# Sheet1.net
KiCad netlist of a schematic drawn in Altium Designer
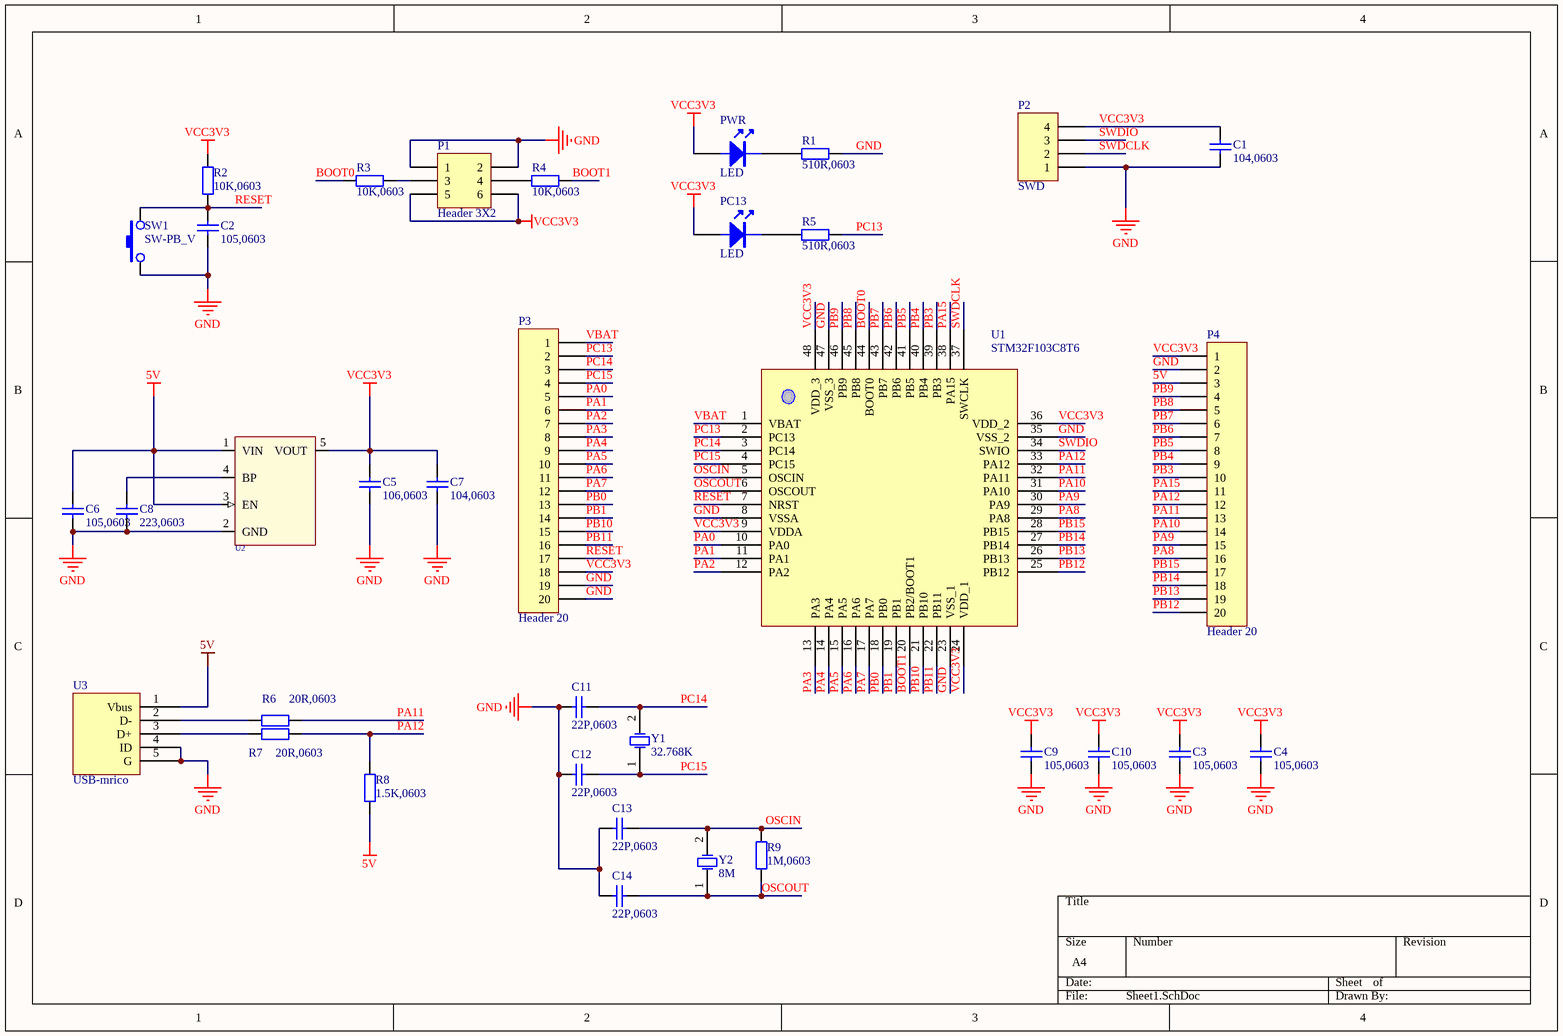
[diagram p0: Sheet1.SchDoc]

(export (version "E")
  (design (tool "Eeschema 10.0.6"))
  (components
    (comp (ref "C1")
      (value "104,0603")
      (footprint "C 0603")
      (description "Capacitor")
      (fields (field (name "PUBLISHER") "Altium Limited"))
      (libsource (lib "STM32F103C8T6") (part "Cap"))
    )
    (comp (ref "C2")
      (value "105,0603")
      (footprint "C 0603")
      (description "Capacitor")
      (fields (field (name "PUBLISHER") "Altium Limited"))
      (libsource (lib "STM32F103C8T6") (part "Cap"))
    )
    (comp (ref "C3")
      (value "105,0603")
      (footprint "C 0603")
      (description "Capacitor")
      (fields (field (name "PUBLISHER") "Altium Limited"))
      (libsource (lib "STM32F103C8T6") (part "Cap"))
    )
    (comp (ref "C4")
      (value "105,0603")
      (footprint "C 0603")
      (description "Capacitor")
      (fields (field (name "PUBLISHER") "Altium Limited"))
      (libsource (lib "STM32F103C8T6") (part "Cap"))
    )
    (comp (ref "C5")
      (value "106,0603")
      (footprint "C 0603")
      (description "Capacitor")
      (fields (field (name "PUBLISHER") "Altium Limited"))
      (libsource (lib "STM32F103C8T6") (part "Cap"))
    )
    (comp (ref "C6")
      (value "105,0603")
      (footprint "C 0603")
      (description "Capacitor")
      (fields (field (name "PUBLISHER") "Altium Limited"))
      (libsource (lib "STM32F103C8T6") (part "Cap"))
    )
    (comp (ref "C7")
      (value "104,0603")
      (footprint "C 0603")
      (description "Capacitor")
      (fields (field (name "PUBLISHER") "Altium Limited"))
      (libsource (lib "STM32F103C8T6") (part "Cap"))
    )
    (comp (ref "C8")
      (value "223,0603")
      (footprint "C 0603")
      (description "Capacitor")
      (fields (field (name "PUBLISHER") "Altium Limited"))
      (libsource (lib "STM32F103C8T6") (part "Cap"))
    )
    (comp (ref "C9")
      (value "105,0603")
      (footprint "C 0603")
      (description "Capacitor")
      (fields (field (name "PUBLISHER") "Altium Limited"))
      (libsource (lib "STM32F103C8T6") (part "Cap"))
    )
    (comp (ref "C10")
      (value "105,0603")
      (footprint "C 0603")
      (description "Capacitor")
      (fields (field (name "PUBLISHER") "Altium Limited"))
      (libsource (lib "STM32F103C8T6") (part "Cap"))
    )
    (comp (ref "C11")
      (value "22P,0603")
      (footprint "C 0603")
      (description "Capacitor")
      (fields (field (name "PUBLISHER") "Altium Limited"))
      (libsource (lib "STM32F103C8T6") (part "Cap"))
    )
    (comp (ref "C12")
      (value "22P,0603")
      (footprint "C 0603")
      (description "Capacitor")
      (fields (field (name "PUBLISHER") "Altium Limited"))
      (libsource (lib "STM32F103C8T6") (part "Cap"))
    )
    (comp (ref "C13")
      (value "22P,0603")
      (footprint "C 0603")
      (description "Capacitor")
      (fields (field (name "PUBLISHER") "Altium Limited"))
      (libsource (lib "STM32F103C8T6") (part "Cap"))
    )
    (comp (ref "C14")
      (value "22P,0603")
      (footprint "C 0603")
      (description "Capacitor")
      (fields (field (name "PUBLISHER") "Altium Limited"))
      (libsource (lib "STM32F103C8T6") (part "Cap"))
    )
    (comp (ref "P1")
      (value "Header 3X2")
      (footprint "HDR-3X2")
      (description "Header, 3-Pin, Dual row")
      (fields (field (name "PUBLISHER") "Altium Limited"))
      (libsource (lib "STM32F103C8T6") (part "Header 3X2"))
    )
    (comp (ref "P2")
      (value "SWD")
      (footprint "HDR-1X4_H")
      (description "Header, 4-Pin")
      (fields (field (name "PUBLISHER") "Altium Limited"))
      (libsource (lib "STM32F103C8T6") (part "Header 4"))
    )
    (comp (ref "P3")
      (value "Header 20")
      (footprint "HDR1X20")
      (description "Header, 20-Pin")
      (fields (field (name "PUBLISHER") "Altium Limited"))
      (libsource (lib "STM32F103C8T6") (part "Header 20"))
    )
    (comp (ref "P4")
      (value "Header 20")
      (footprint "HDR1X20")
      (description "Header, 20-Pin")
      (fields (field (name "PUBLISHER") "Altium Limited"))
      (libsource (lib "") (part "Header 20_1"))
    )
    (comp (ref "PC13") (value "LED") (footprint "LED 0805G") (libsource (lib "STM32F103C8T6") (part "LED")))
    (comp (ref "PWR") (value "LED") (footprint "LED 0805G") (libsource (lib "STM32F103C8T6") (part "LED")))
    (comp (ref "R1")
      (value "510R,0603")
      (footprint "R 0603")
      (description "Resistor")
      (fields (field (name "PUBLISHER") "Altium Limited"))
      (libsource (lib "STM32F103C8T6") (part "Res2"))
    )
    (comp (ref "R2")
      (value "10K,0603")
      (footprint "R 0603")
      (description "Resistor")
      (fields (field (name "PUBLISHER") "Altium Limited"))
      (libsource (lib "") (part "Res2_1"))
    )
    (comp (ref "R3")
      (value "10K,0603")
      (footprint "R 0603")
      (description "Resistor")
      (fields (field (name "PUBLISHER") "Altium Limited"))
      (libsource (lib "STM32F103C8T6") (part "Res2"))
    )
    (comp (ref "R4")
      (value "10K,0603")
      (footprint "R 0603")
      (description "Resistor")
      (fields (field (name "PUBLISHER") "Altium Limited"))
      (libsource (lib "STM32F103C8T6") (part "Res2"))
    )
    (comp (ref "R5")
      (value "510R,0603")
      (footprint "R 0603")
      (description "Resistor")
      (fields (field (name "PUBLISHER") "Altium Limited"))
      (libsource (lib "STM32F103C8T6") (part "Res2"))
    )
    (comp (ref "R6")
      (value "20R,0603")
      (footprint "R 0603")
      (description "Resistor")
      (fields (field (name "PUBLISHER") "Altium Limited"))
      (libsource (lib "STM32F103C8T6") (part "Res2"))
    )
    (comp (ref "R7")
      (value "20R,0603")
      (footprint "R 0603")
      (description "Resistor")
      (fields (field (name "PUBLISHER") "Altium Limited"))
      (libsource (lib "STM32F103C8T6") (part "Res2"))
    )
    (comp (ref "R8")
      (value "1.5K,0603")
      (footprint "R 0603")
      (description "Resistor")
      (fields (field (name "PUBLISHER") "Altium Limited"))
      (libsource (lib "") (part "Res2_1"))
    )
    (comp (ref "R9")
      (value "1M,0603")
      (footprint "R 0603")
      (description "Resistor")
      (fields (field (name "PUBLISHER") "Altium Limited"))
      (libsource (lib "") (part "Res2_1"))
    )
    (comp (ref "SW1")
      (value "SW-PB_V")
      (footprint "TSW SMD-3*6*2.5")
      (description "SWITCH")
      (libsource (lib "STM32F103C8T6") (part "SW-PB_V"))
    )
    (comp (ref "U1")
      (value "STM32F103C8T6")
      (footprint "TQFP48 7x7_L")
      (libsource (lib "STM32F103C8T6") (part "STM32F103C8T6"))
    )
    (comp (ref "U2")
      (value "RT9193")
      (footprint "SOT23-5L")
      (fields (field (name "ICA_PARTNUM") "$$2191094$$RT9193-15CU5") (field (name "PART NUMBER") "TMP-13"))
      (libsource (lib "STM32F103C8T6") (part "RT9193X_5P"))
    )
    (comp (ref "U3")
      (value "USB-mrico")
      (footprint "USB-micro_B")
      (libsource (lib "PCB_Project_4") (part "usb-STM"))
    )
    (comp (ref "Y1")
      (value "32.768K")
      (footprint "XTAL-3215")
      (description "Crystal Oscillator")
      (fields (field (name "PUBLISHER") "Altium Limited"))
      (libsource (lib "PCB_Project_4") (part "XTAL"))
    )
    (comp (ref "Y2")
      (value "8M")
      (footprint "STM32F103C8T6核心板:XTAL-5032")
      (description "Crystal Oscillator")
      (fields (field (name "PUBLISHER") "Altium Limited"))
      (libsource (lib "PCB_Project_4") (part "XTAL"))
    )
  )
  (nets
    (net (code "1") (name "/BOOT0") (class "Default")
      (node (ref "R3") (pin "1") (pinfunction "1_1") (pintype "passive"))
      (node (ref "U1") (pin "44") (pinfunction "BOOT0_44") (pintype "passive"))
    )
    (net (code "2") (name "/BOOT1") (class "Default")
      (node (ref "R4") (pin "2") (pinfunction "2_2") (pintype "passive"))
      (node (ref "U1") (pin "20") (pinfunction "PB2/BOOT1_20") (pintype "passive"))
    )
    (net (code "3") (name "/OSCIN") (class "Default")
      (node (ref "C13") (pin "1") (pinfunction "1_1") (pintype "passive"))
      (node (ref "R9") (pin "2") (pinfunction "2_2") (pintype "passive"))
      (node (ref "U1") (pin "5") (pinfunction "OSCIN_5") (pintype "passive"))
      (node (ref "Y2") (pin "2") (pinfunction "OSC2_2") (pintype "passive"))
    )
    (net (code "4") (name "/OSCOUT") (class "Default")
      (node (ref "C14") (pin "1") (pinfunction "1_1") (pintype "passive"))
      (node (ref "R9") (pin "1") (pinfunction "1_1") (pintype "passive"))
      (node (ref "U1") (pin "6") (pinfunction "OSCOUT_6") (pintype "passive"))
      (node (ref "Y2") (pin "1") (pinfunction "OSC1_1") (pintype "passive"))
    )
    (net (code "5") (name "/PA0") (class "Default")
      (node (ref "P3") (pin "5") (pinfunction "5_5") (pintype "passive"))
      (node (ref "U1") (pin "10") (pinfunction "PA0_10") (pintype "passive"))
    )
    (net (code "6") (name "/PA1") (class "Default")
      (node (ref "P3") (pin "6") (pinfunction "6_6") (pintype "passive"))
      (node (ref "U1") (pin "11") (pinfunction "PA1_11") (pintype "passive"))
    )
    (net (code "7") (name "/PA2") (class "Default")
      (node (ref "P3") (pin "7") (pinfunction "7_7") (pintype "passive"))
      (node (ref "U1") (pin "12") (pinfunction "PA2_12") (pintype "passive"))
    )
    (net (code "8") (name "/PA3") (class "Default")
      (node (ref "P3") (pin "8") (pinfunction "8_8") (pintype "passive"))
      (node (ref "U1") (pin "13") (pinfunction "PA3_13") (pintype "passive"))
    )
    (net (code "9") (name "/PA4") (class "Default")
      (node (ref "P3") (pin "9") (pinfunction "9_9") (pintype "passive"))
      (node (ref "U1") (pin "14") (pinfunction "PA4_14") (pintype "passive"))
    )
    (net (code "10") (name "/PA5") (class "Default")
      (node (ref "P3") (pin "10") (pinfunction "10_10") (pintype "passive"))
      (node (ref "U1") (pin "15") (pinfunction "PA5_15") (pintype "passive"))
    )
    (net (code "11") (name "/PA6") (class "Default")
      (node (ref "P3") (pin "11") (pinfunction "11_11") (pintype "passive"))
      (node (ref "U1") (pin "16") (pinfunction "PA6_16") (pintype "passive"))
    )
    (net (code "12") (name "/PA7") (class "Default")
      (node (ref "P3") (pin "12") (pinfunction "12_12") (pintype "passive"))
      (node (ref "U1") (pin "17") (pinfunction "PA7_17") (pintype "passive"))
    )
    (net (code "13") (name "/PA8") (class "Default")
      (node (ref "P4") (pin "16") (pinfunction "16_16") (pintype "passive"))
      (node (ref "U1") (pin "29") (pinfunction "PA8_29") (pintype "passive"))
    )
    (net (code "14") (name "/PA9") (class "Default")
      (node (ref "P4") (pin "15") (pinfunction "15_15") (pintype "passive"))
      (node (ref "U1") (pin "30") (pinfunction "PA9_30") (pintype "passive"))
    )
    (net (code "15") (name "/PA10") (class "Default")
      (node (ref "P4") (pin "14") (pinfunction "14_14") (pintype "passive"))
      (node (ref "U1") (pin "31") (pinfunction "PA10_31") (pintype "passive"))
    )
    (net (code "16") (name "/PA11") (class "Default")
      (node (ref "P4") (pin "13") (pinfunction "13_13") (pintype "passive"))
      (node (ref "R6") (pin "2") (pinfunction "2_2") (pintype "passive"))
      (node (ref "U1") (pin "32") (pinfunction "PA11_32") (pintype "passive"))
    )
    (net (code "17") (name "/PA12") (class "Default")
      (node (ref "P4") (pin "12") (pinfunction "12_12") (pintype "passive"))
      (node (ref "R7") (pin "2") (pinfunction "2_2") (pintype "passive"))
      (node (ref "R8") (pin "2") (pinfunction "2_2") (pintype "passive"))
      (node (ref "U1") (pin "33") (pinfunction "PA12_33") (pintype "passive"))
    )
    (net (code "18") (name "/PA15") (class "Default")
      (node (ref "P4") (pin "11") (pinfunction "11_11") (pintype "passive"))
      (node (ref "U1") (pin "38") (pinfunction "PA15_38") (pintype "passive"))
    )
    (net (code "19") (name "/PB0") (class "Default")
      (node (ref "P3") (pin "13") (pinfunction "13_13") (pintype "passive"))
      (node (ref "U1") (pin "18") (pinfunction "PB0_18") (pintype "passive"))
    )
    (net (code "20") (name "/PB1") (class "Default")
      (node (ref "P3") (pin "14") (pinfunction "14_14") (pintype "passive"))
      (node (ref "U1") (pin "19") (pinfunction "PB1_19") (pintype "passive"))
    )
    (net (code "21") (name "/PB3") (class "Default")
      (node (ref "P4") (pin "10") (pinfunction "10_10") (pintype "passive"))
      (node (ref "U1") (pin "39") (pinfunction "PB3_39") (pintype "passive"))
    )
    (net (code "22") (name "/PB4") (class "Default")
      (node (ref "P4") (pin "9") (pinfunction "9_9") (pintype "passive"))
      (node (ref "U1") (pin "40") (pinfunction "PB4_40") (pintype "passive"))
    )
    (net (code "23") (name "/PB5") (class "Default")
      (node (ref "P4") (pin "8") (pinfunction "8_8") (pintype "passive"))
      (node (ref "U1") (pin "41") (pinfunction "PB5_41") (pintype "passive"))
    )
    (net (code "24") (name "/PB6") (class "Default")
      (node (ref "P4") (pin "7") (pinfunction "7_7") (pintype "passive"))
      (node (ref "U1") (pin "42") (pinfunction "PB6_42") (pintype "passive"))
    )
    (net (code "25") (name "/PB7") (class "Default")
      (node (ref "P4") (pin "6") (pinfunction "6_6") (pintype "passive"))
      (node (ref "U1") (pin "43") (pinfunction "PB7_43") (pintype "passive"))
    )
    (net (code "26") (name "/PB8") (class "Default")
      (node (ref "P4") (pin "5") (pinfunction "5_5") (pintype "passive"))
      (node (ref "U1") (pin "45") (pinfunction "PB8_45") (pintype "passive"))
    )
    (net (code "27") (name "/PB9") (class "Default")
      (node (ref "P4") (pin "4") (pinfunction "4_4") (pintype "passive"))
      (node (ref "U1") (pin "46") (pinfunction "PB9_46") (pintype "passive"))
    )
    (net (code "28") (name "/PB10") (class "Default")
      (node (ref "P3") (pin "15") (pinfunction "15_15") (pintype "passive"))
      (node (ref "U1") (pin "21") (pinfunction "PB10_21") (pintype "passive"))
    )
    (net (code "29") (name "/PB11") (class "Default")
      (node (ref "P3") (pin "16") (pinfunction "16_16") (pintype "passive"))
      (node (ref "U1") (pin "22") (pinfunction "PB11_22") (pintype "passive"))
    )
    (net (code "30") (name "/PB12") (class "Default")
      (node (ref "P4") (pin "20") (pinfunction "20_20") (pintype "passive"))
      (node (ref "U1") (pin "25") (pinfunction "PB12_25") (pintype "passive"))
    )
    (net (code "31") (name "/PB13") (class "Default")
      (node (ref "P4") (pin "19") (pinfunction "19_19") (pintype "passive"))
      (node (ref "U1") (pin "26") (pinfunction "PB13_26") (pintype "passive"))
    )
    (net (code "32") (name "/PB14") (class "Default")
      (node (ref "P4") (pin "18") (pinfunction "18_18") (pintype "passive"))
      (node (ref "U1") (pin "27") (pinfunction "PB14_27") (pintype "passive"))
    )
    (net (code "33") (name "/PB15") (class "Default")
      (node (ref "P4") (pin "17") (pinfunction "17_17") (pintype "passive"))
      (node (ref "U1") (pin "28") (pinfunction "PB15_28") (pintype "passive"))
    )
    (net (code "34") (name "/PC13") (class "Default")
      (node (ref "P3") (pin "2") (pinfunction "2_2") (pintype "passive"))
      (node (ref "R5") (pin "2") (pinfunction "2_2") (pintype "passive"))
      (node (ref "U1") (pin "2") (pinfunction "PC13_2") (pintype "passive"))
    )
    (net (code "35") (name "/PC14") (class "Default")
      (node (ref "C11") (pin "1") (pinfunction "1_1") (pintype "passive"))
      (node (ref "P3") (pin "3") (pinfunction "3_3") (pintype "passive"))
      (node (ref "U1") (pin "3") (pinfunction "PC14_3") (pintype "passive"))
      (node (ref "Y1") (pin "2") (pinfunction "OSC2_2") (pintype "passive"))
    )
    (net (code "36") (name "/PC15") (class "Default")
      (node (ref "C12") (pin "1") (pinfunction "1_1") (pintype "passive"))
      (node (ref "P3") (pin "4") (pinfunction "4_4") (pintype "passive"))
      (node (ref "U1") (pin "4") (pinfunction "PC15_4") (pintype "passive"))
      (node (ref "Y1") (pin "1") (pinfunction "OSC1_1") (pintype "passive"))
    )
    (net (code "37") (name "/RESET") (class "Default")
      (node (ref "C2") (pin "2") (pinfunction "2_2") (pintype "passive"))
      (node (ref "P3") (pin "17") (pinfunction "17_17") (pintype "passive"))
      (node (ref "R2") (pin "1") (pinfunction "1_1") (pintype "passive"))
      (node (ref "SW1") (pin "2") (pinfunction "2_2") (pintype "passive"))
      (node (ref "U1") (pin "7") (pinfunction "NRST_7") (pintype "passive"))
    )
    (net (code "38") (name "/SWDCLK") (class "Default")
      (node (ref "P2") (pin "2") (pinfunction "2_2") (pintype "passive"))
      (node (ref "U1") (pin "37") (pinfunction "SWCLK_37") (pintype "passive"))
    )
    (net (code "39") (name "/SWDIO") (class "Default")
      (node (ref "P2") (pin "3") (pinfunction "3_3") (pintype "passive"))
      (node (ref "U1") (pin "34") (pinfunction "SWIO_34") (pintype "passive"))
    )
    (net (code "40") (name "/VBAT") (class "Default")
      (node (ref "P3") (pin "1") (pinfunction "1_1") (pintype "passive"))
      (node (ref "U1") (pin "1") (pinfunction "VBAT_1") (pintype "passive"))
    )
    (net (code "41") (name "5V") (class "Default")
      (node (ref "C6") (pin "2") (pinfunction "2_2") (pintype "passive"))
      (node (ref "P4") (pin "3") (pinfunction "3_3") (pintype "passive"))
      (node (ref "R8") (pin "1") (pinfunction "1_1") (pintype "passive"))
      (node (ref "U2") (pin "1") (pinfunction "VIN_1") (pintype "power_in"))
      (node (ref "U2") (pin "3") (pinfunction "EN_3") (pintype "input"))
      (node (ref "U3") (pin "1") (pinfunction "Vbus_1") (pintype "passive"))
    )
    (net (code "42") (name "GND") (class "Default")
      (node (ref "C1") (pin "1") (pinfunction "1_1") (pintype "passive"))
      (node (ref "C10") (pin "1") (pinfunction "1_1") (pintype "passive"))
      (node (ref "C11") (pin "2") (pinfunction "2_2") (pintype "passive"))
      (node (ref "C12") (pin "2") (pinfunction "2_2") (pintype "passive"))
      (node (ref "C13") (pin "2") (pinfunction "2_2") (pintype "passive"))
      (node (ref "C14") (pin "2") (pinfunction "2_2") (pintype "passive"))
      (node (ref "C2") (pin "1") (pinfunction "1_1") (pintype "passive"))
      (node (ref "C3") (pin "1") (pinfunction "1_1") (pintype "passive"))
      (node (ref "C4") (pin "1") (pinfunction "1_1") (pintype "passive"))
      (node (ref "C5") (pin "2") (pinfunction "2_2") (pintype "passive"))
      (node (ref "C6") (pin "1") (pinfunction "1_1") (pintype "passive"))
      (node (ref "C7") (pin "1") (pinfunction "1_1") (pintype "passive"))
      (node (ref "C8") (pin "1") (pinfunction "1_1") (pintype "passive"))
      (node (ref "C9") (pin "1") (pinfunction "1_1") (pintype "passive"))
      (node (ref "P1") (pin "1") (pinfunction "1_1") (pintype "passive"))
      (node (ref "P1") (pin "2") (pinfunction "2_2") (pintype "passive"))
      (node (ref "P2") (pin "1") (pinfunction "1_1") (pintype "passive"))
      (node (ref "P3") (pin "19") (pinfunction "19_19") (pintype "passive"))
      (node (ref "P3") (pin "20") (pinfunction "20_20") (pintype "passive"))
      (node (ref "P4") (pin "2") (pinfunction "2_2") (pintype "passive"))
      (node (ref "R1") (pin "2") (pinfunction "2_2") (pintype "passive"))
      (node (ref "SW1") (pin "1") (pinfunction "1_1") (pintype "passive"))
      (node (ref "U1") (pin "23") (pinfunction "VSS_1_23") (pintype "passive"))
      (node (ref "U1") (pin "35") (pinfunction "VSS_2_35") (pintype "passive"))
      (node (ref "U1") (pin "47") (pinfunction "VSS_3_47") (pintype "passive"))
      (node (ref "U1") (pin "8") (pinfunction "VSSA_8") (pintype "passive"))
      (node (ref "U2") (pin "2") (pinfunction "GND_2") (pintype "power_in"))
      (node (ref "U3") (pin "4") (pinfunction "ID_4") (pintype "passive"))
      (node (ref "U3") (pin "5") (pinfunction "G_5") (pintype "passive"))
    )
    (net (code "43") (name "Net-(P1-Pad3)") (class "Default")
      (node (ref "P1") (pin "3") (pinfunction "3_3") (pintype "passive"))
      (node (ref "R3") (pin "2") (pinfunction "2_2") (pintype "passive"))
    )
    (net (code "44") (name "Net-(P1-Pad4)") (class "Default")
      (node (ref "P1") (pin "4") (pinfunction "4_4") (pintype "passive"))
      (node (ref "R4") (pin "1") (pinfunction "1_1") (pintype "passive"))
    )
    (net (code "45") (name "Net-(PC13-Pad2)") (class "Default")
      (node (ref "PC13") (pin "2") (pinfunction "2_2") (pintype "passive"))
      (node (ref "R5") (pin "1") (pinfunction "1_1") (pintype "passive"))
    )
    (net (code "46") (name "Net-(PWR-Pad2)") (class "Default")
      (node (ref "PWR") (pin "2") (pinfunction "2_2") (pintype "passive"))
      (node (ref "R1") (pin "1") (pinfunction "1_1") (pintype "passive"))
    )
    (net (code "47") (name "Net-(U2-BP)") (class "Default")
      (node (ref "C8") (pin "2") (pinfunction "2_2") (pintype "passive"))
      (node (ref "U2") (pin "4") (pinfunction "BP_4") (pintype "passive"))
    )
    (net (code "48") (name "Net-(U3-D+)") (class "Default")
      (node (ref "R7") (pin "1") (pinfunction "1_1") (pintype "passive"))
      (node (ref "U3") (pin "3") (pinfunction "D+_3") (pintype "passive"))
    )
    (net (code "49") (name "Net-(U3-D-)") (class "Default")
      (node (ref "R6") (pin "1") (pinfunction "1_1") (pintype "passive"))
      (node (ref "U3") (pin "2") (pinfunction "D-_2") (pintype "passive"))
    )
    (net (code "50") (name "VCC3V3") (class "Default")
      (node (ref "C1") (pin "2") (pinfunction "2_2") (pintype "passive"))
      (node (ref "C10") (pin "2") (pinfunction "2_2") (pintype "passive"))
      (node (ref "C3") (pin "2") (pinfunction "2_2") (pintype "passive"))
      (node (ref "C4") (pin "2") (pinfunction "2_2") (pintype "passive"))
      (node (ref "C5") (pin "1") (pinfunction "1_1") (pintype "passive"))
      (node (ref "C7") (pin "2") (pinfunction "2_2") (pintype "passive"))
      (node (ref "C9") (pin "2") (pinfunction "2_2") (pintype "passive"))
      (node (ref "P1") (pin "5") (pinfunction "5_5") (pintype "passive"))
      (node (ref "P1") (pin "6") (pinfunction "6_6") (pintype "passive"))
      (node (ref "P2") (pin "4") (pinfunction "4_4") (pintype "passive"))
      (node (ref "P3") (pin "18") (pinfunction "18_18") (pintype "passive"))
      (node (ref "P4") (pin "1") (pinfunction "1_1") (pintype "passive"))
      (node (ref "PC13") (pin "1") (pinfunction "1_1") (pintype "passive"))
      (node (ref "PWR") (pin "1") (pinfunction "1_1") (pintype "passive"))
      (node (ref "R2") (pin "2") (pinfunction "2_2") (pintype "passive"))
      (node (ref "U1") (pin "24") (pinfunction "VDD_1_24") (pintype "passive"))
      (node (ref "U1") (pin "36") (pinfunction "VDD_2_36") (pintype "passive"))
      (node (ref "U1") (pin "48") (pinfunction "VDD_3_48") (pintype "passive"))
      (node (ref "U1") (pin "9") (pinfunction "VDDA_9") (pintype "passive"))
      (node (ref "U2") (pin "5") (pinfunction "VOUT_5") (pintype "power_in"))
    )
  )
)
